# honda-z50a-regulator.net
KiCad netlist of a schematic drawn in EAGLE
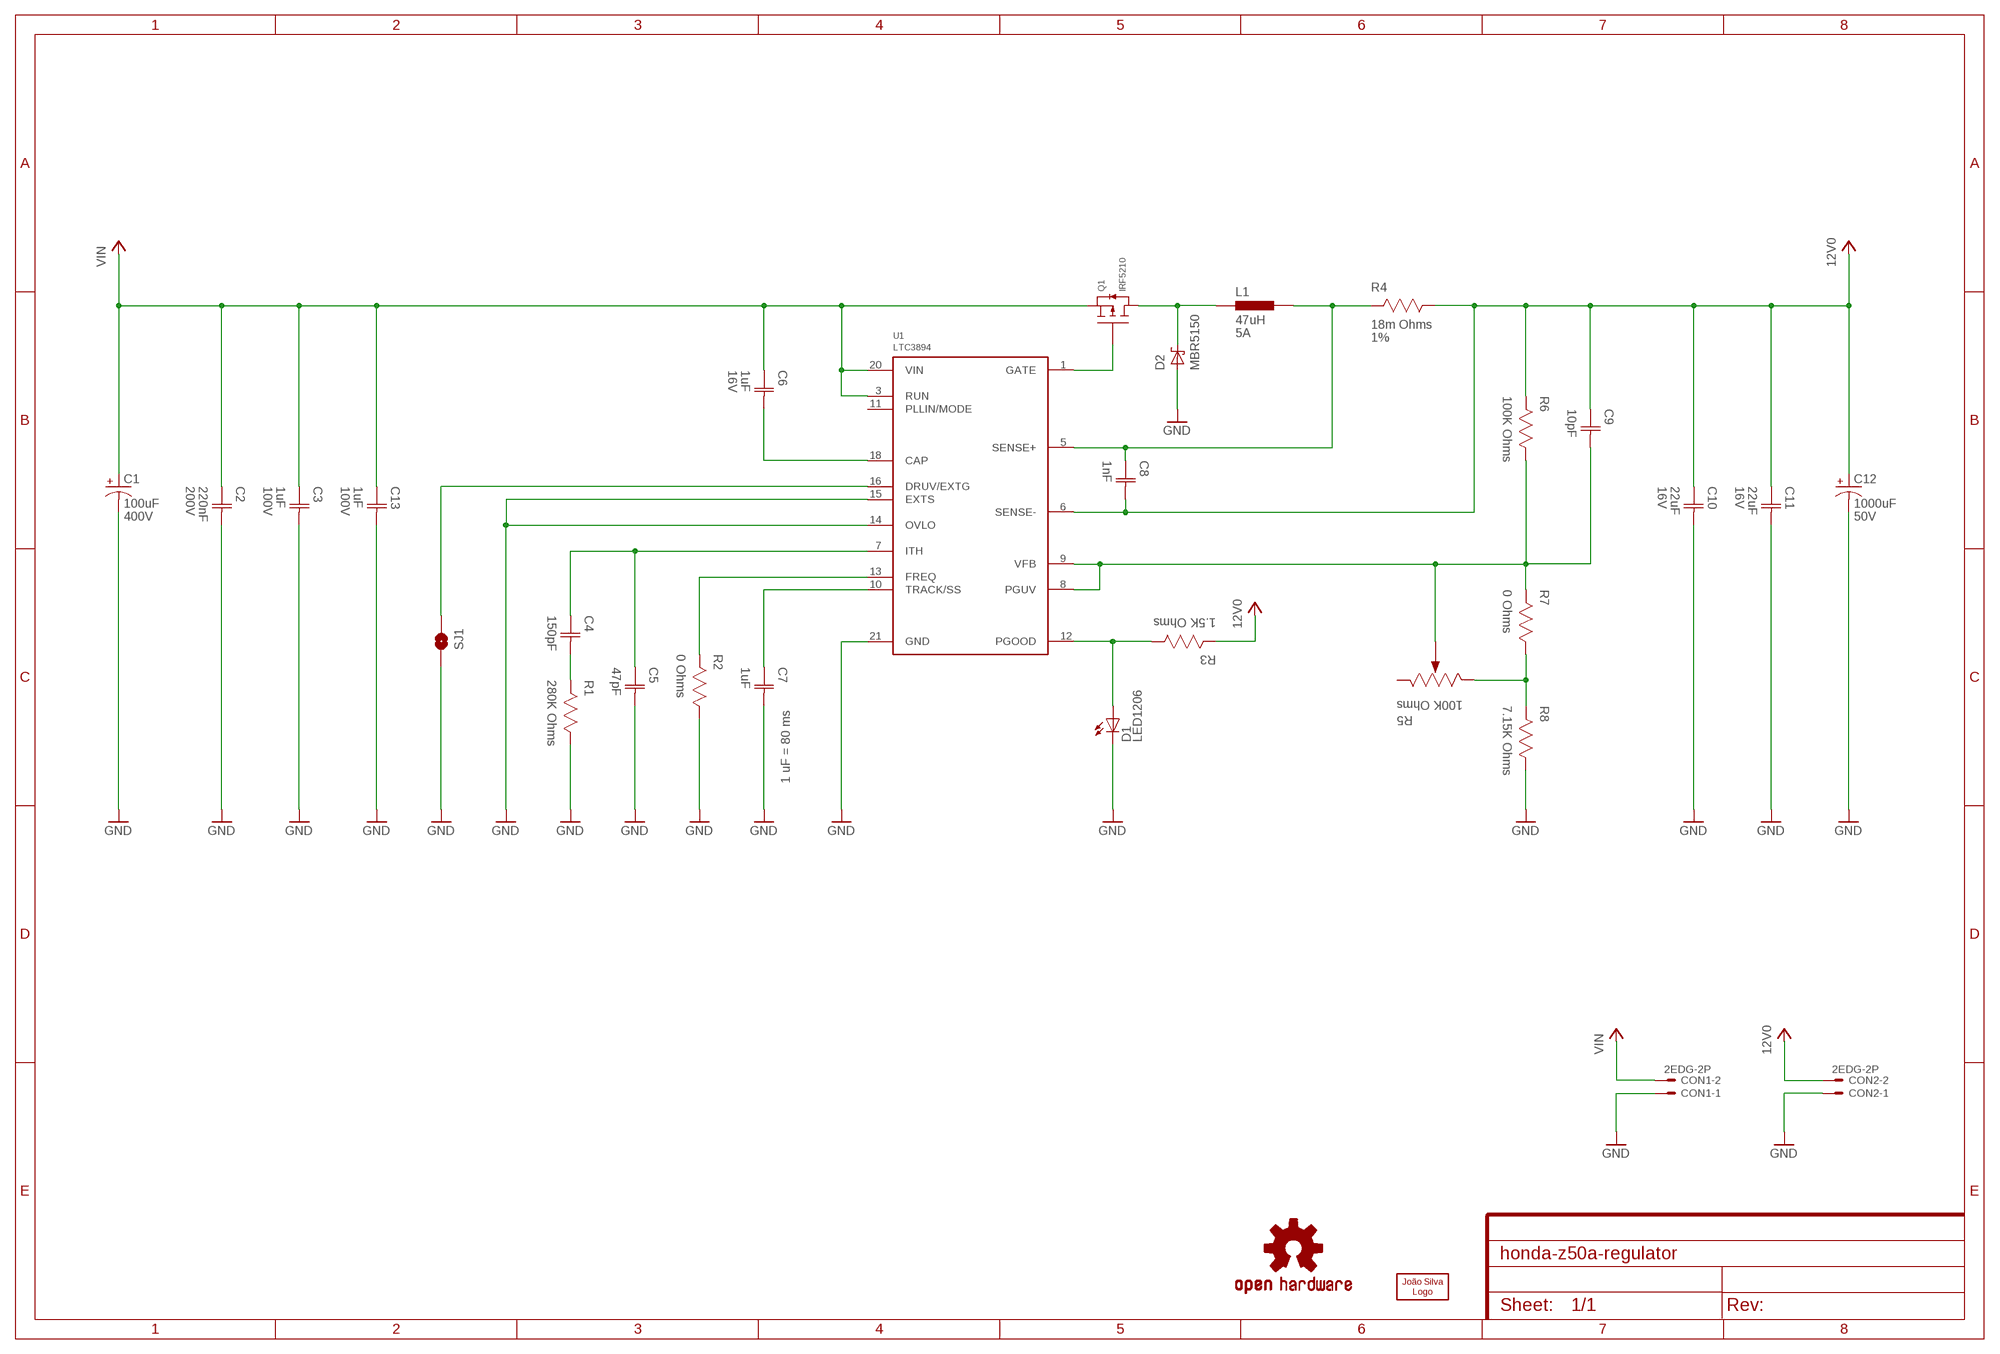
[diagram p0: schematic, sheet 1]

(export (version "E")
  (design (tool "Eeschema 10.0.6"))
  (components
    (comp (ref "C1")
      (value "100uF")
      (footprint "eagle-import:EL-CAP-18MM")
      (fields (field (name "VOLTAGE") "400V"))
      (libsource (lib "eagle-import") (part "ELETROLITIC-CAPACITOR-18MM"))
    )
    (comp (ref "C2")
      (value "220nF")
      (footprint "eagle-import:CAP1206")
      (fields (field (name "VOLTAGE") "200V"))
      (libsource (lib "eagle-import") (part "CAPACITOR-1206"))
    )
    (comp (ref "C3")
      (value "1uF")
      (footprint "eagle-import:CAP1206")
      (fields (field (name "VOLTAGE") "100V"))
      (libsource (lib "eagle-import") (part "CAPACITOR-1206"))
    )
    (comp (ref "C4")
      (value "150pF")
      (footprint "eagle-import:CAP0603")
      (libsource (lib "eagle-import") (part "CAPACITOR-0603"))
    )
    (comp (ref "C5")
      (value "47pF")
      (footprint "eagle-import:CAP0603")
      (libsource (lib "eagle-import") (part "CAPACITOR-0603"))
    )
    (comp (ref "C6")
      (value "1uF")
      (footprint "eagle-import:CAP0603")
      (fields (field (name "VOLTAGE") "16V"))
      (libsource (lib "eagle-import") (part "CAPACITOR-0603"))
    )
    (comp (ref "C7")
      (value "1uF")
      (footprint "eagle-import:CAP0603")
      (libsource (lib "eagle-import") (part "CAPACITOR-0603"))
    )
    (comp (ref "C8")
      (value "1nF")
      (footprint "eagle-import:CAP0603")
      (libsource (lib "eagle-import") (part "CAPACITOR-0603"))
    )
    (comp (ref "C9")
      (value "10pF")
      (footprint "eagle-import:CAP0603")
      (libsource (lib "eagle-import") (part "CAPACITOR-0603"))
    )
    (comp (ref "C10")
      (value "22uF")
      (footprint "eagle-import:CAP1206")
      (fields (field (name "VOLTAGE") "16V"))
      (libsource (lib "eagle-import") (part "CAPACITOR-1206"))
    )
    (comp (ref "C11")
      (value "22uF")
      (footprint "eagle-import:CAP1206")
      (fields (field (name "VOLTAGE") "16V"))
      (libsource (lib "eagle-import") (part "CAPACITOR-1206"))
    )
    (comp (ref "C12")
      (value "1000uF")
      (footprint "eagle-import:EL-CAP-13MM")
      (fields (field (name "VOLTAGE") "50V"))
      (libsource (lib "eagle-import") (part "ELETROLITIC-CAPACITOR-13MM"))
    )
    (comp (ref "C13")
      (value "1uF")
      (footprint "eagle-import:CAP1206")
      (fields (field (name "VOLTAGE") "100V"))
      (libsource (lib "eagle-import") (part "CAPACITOR-1206"))
    )
    (comp (ref "CON1")
      (value "2EDG-2P")
      (footprint "eagle-import:2EDG-2P")
      (libsource (lib "eagle-import") (part "2EDG-2P"))
    )
    (comp (ref "CON2")
      (value "2EDG-2P")
      (footprint "eagle-import:2EDG-2P")
      (libsource (lib "eagle-import") (part "2EDG-2P"))
    )
    (comp (ref "D1")
      (value "LED1206")
      (footprint "eagle-import:1206")
      (libsource (lib "eagle-import") (part "LED1206"))
    )
    (comp (ref "D2")
      (value "MBR5150")
      (footprint "eagle-import:DO201AD")
      (libsource (lib "eagle-import") (part "MBR5150"))
    )
    (comp (ref "L1")
      (value "47uH")
      (footprint "eagle-import:IND1365")
      (fields (field (name "CURRENT") "5A"))
      (libsource (lib "eagle-import") (part "INDUCTOR-13X13X6.5MM"))
    )
    (comp (ref "LOGO1")
      (value "OSHW-LOGOS")
      (footprint "eagle-import:OSHW-LOGO-S")
      (libsource (lib "eagle-import") (part "OSHW-LOGOS"))
    )
    (comp (ref "LOGO2")
      (value "JS-5MM")
      (footprint "eagle-import:JS_5MM")
      (libsource (lib "eagle-import") (part "JS-5MM"))
    )
    (comp (ref "Q1")
      (value "IRF5210")
      (footprint "eagle-import:TO262-HS")
      (libsource (lib "eagle-import") (part "IRF5210"))
    )
    (comp (ref "R1")
      (value "280K Ohms")
      (footprint "eagle-import:RES0603")
      (libsource (lib "eagle-import") (part "RESISTOR-0603"))
    )
    (comp (ref "R2")
      (value "0 Ohms")
      (footprint "eagle-import:RES0603")
      (libsource (lib "eagle-import") (part "RESISTOR-0603"))
    )
    (comp (ref "R3")
      (value "1.5K Ohms")
      (footprint "eagle-import:RES0603")
      (libsource (lib "eagle-import") (part "RESISTOR-0603"))
    )
    (comp (ref "R4")
      (value "18m Ohms")
      (footprint "eagle-import:RES2512")
      (fields (field (name "TOLERANCE") "1%"))
      (libsource (lib "eagle-import") (part "RESISTOR-2512"))
    )
    (comp (ref "R5")
      (value "100K Ohms")
      (footprint "eagle-import:TRIMMER")
      (libsource (lib "eagle-import") (part "POTENTIOMETER-TH"))
    )
    (comp (ref "R6")
      (value "100K Ohms")
      (footprint "eagle-import:RES0603")
      (libsource (lib "eagle-import") (part "RESISTOR-0603"))
    )
    (comp (ref "R7")
      (value "0 Ohms")
      (footprint "eagle-import:RES0603")
      (libsource (lib "eagle-import") (part "RESISTOR-0603"))
    )
    (comp (ref "R8")
      (value "7.15K Ohms")
      (footprint "eagle-import:RES0603")
      (libsource (lib "eagle-import") (part "RESISTOR-0603"))
    )
    (comp (ref "SJ1")
      (value "SJS")
      (footprint "eagle-import:SJ_S")
      (libsource (lib "eagle-import") (part "SJS"))
    )
    (comp (ref "U1")
      (value "LTC3894")
      (footprint "eagle-import:MSOP20_HV_EP")
      (libsource (lib "eagle-import") (part "LTC3894"))
    )
  )
  (nets
    (net (code "1") (name "12V0") (class "Default")
      (node (ref "C10") (pin "1") (pinfunction "C1_1") (pintype "passive"))
      (node (ref "C11") (pin "1") (pinfunction "C1_1") (pintype "passive"))
      (node (ref "C12") (pin "+") (pinfunction "+_+") (pintype "passive"))
      (node (ref "C8") (pin "2") (pinfunction "C2_2") (pintype "passive"))
      (node (ref "C9") (pin "1") (pinfunction "C1_1") (pintype "passive"))
      (node (ref "CON2") (pin "P$2") (pinfunction "S_P$2") (pintype "passive"))
      (node (ref "R3") (pin "2") (pinfunction "2_2") (pintype "passive"))
      (node (ref "R4") (pin "1") (pinfunction "1_1") (pintype "passive"))
      (node (ref "R6") (pin "2") (pinfunction "2_2") (pintype "passive"))
      (node (ref "U1") (pin "6") (pinfunction "SENSE-_6") (pintype "bidirectional"))
    )
    (net (code "2") (name "GND") (class "Default")
      (node (ref "C1") (pin "-") (pinfunction "-_-") (pintype "passive"))
      (node (ref "C10") (pin "2") (pinfunction "C2_2") (pintype "passive"))
      (node (ref "C11") (pin "2") (pinfunction "C2_2") (pintype "passive"))
      (node (ref "C12") (pin "-") (pinfunction "-_-") (pintype "passive"))
      (node (ref "C13") (pin "2") (pinfunction "C2_2") (pintype "passive"))
      (node (ref "C2") (pin "2") (pinfunction "C2_2") (pintype "passive"))
      (node (ref "C3") (pin "2") (pinfunction "C2_2") (pintype "passive"))
      (node (ref "C5") (pin "2") (pinfunction "C2_2") (pintype "passive"))
      (node (ref "C7") (pin "2") (pinfunction "C2_2") (pintype "passive"))
      (node (ref "CON1") (pin "P$1") (pinfunction "S_P$1") (pintype "passive"))
      (node (ref "CON2") (pin "P$1") (pinfunction "S_P$1") (pintype "passive"))
      (node (ref "D1") (pin "C") (pinfunction "C_C") (pintype "passive"))
      (node (ref "D2") (pin "A") (pinfunction "A_A") (pintype "passive"))
      (node (ref "R1") (pin "1") (pinfunction "1_1") (pintype "passive"))
      (node (ref "R2") (pin "1") (pinfunction "1_1") (pintype "passive"))
      (node (ref "R8") (pin "1") (pinfunction "1_1") (pintype "passive"))
      (node (ref "SJ1") (pin "2") (pinfunction "2_2") (pintype "passive"))
      (node (ref "U1") (pin "14") (pinfunction "OVLO_14") (pintype "bidirectional"))
      (node (ref "U1") (pin "15") (pinfunction "EXTS_15") (pintype "bidirectional"))
      (node (ref "U1") (pin "21") (pinfunction "GND_21") (pintype "bidirectional"))
    )
    (net (code "3") (name "Net-(C4-C1)") (class "Default")
      (node (ref "C4") (pin "1") (pinfunction "C1_1") (pintype "passive"))
      (node (ref "C5") (pin "1") (pinfunction "C1_1") (pintype "passive"))
      (node (ref "U1") (pin "7") (pinfunction "ITH_7") (pintype "bidirectional"))
    )
    (net (code "4") (name "Net-(C4-C2)") (class "Default")
      (node (ref "C4") (pin "2") (pinfunction "C2_2") (pintype "passive"))
      (node (ref "R1") (pin "2") (pinfunction "2_2") (pintype "passive"))
    )
    (net (code "5") (name "Net-(C6-C2)") (class "Default")
      (node (ref "C6") (pin "2") (pinfunction "C2_2") (pintype "passive"))
      (node (ref "U1") (pin "18") (pinfunction "CAP_18") (pintype "bidirectional"))
    )
    (net (code "6") (name "Net-(C7-C1)") (class "Default")
      (node (ref "C7") (pin "1") (pinfunction "C1_1") (pintype "passive"))
      (node (ref "U1") (pin "10") (pinfunction "TRACK/SS_10") (pintype "bidirectional"))
    )
    (net (code "7") (name "Net-(C8-C1)") (class "Default")
      (node (ref "C8") (pin "1") (pinfunction "C1_1") (pintype "passive"))
      (node (ref "L1") (pin "2") (pinfunction "2_2") (pintype "passive"))
      (node (ref "R4") (pin "2") (pinfunction "2_2") (pintype "passive"))
      (node (ref "U1") (pin "5") (pinfunction "SENSE+_5") (pintype "bidirectional"))
    )
    (net (code "8") (name "Net-(C9-C2)") (class "Default")
      (node (ref "C9") (pin "2") (pinfunction "C2_2") (pintype "passive"))
      (node (ref "R5") (pin "S") (pinfunction "WIPER_S") (pintype "passive"))
      (node (ref "R6") (pin "1") (pinfunction "1_1") (pintype "passive"))
      (node (ref "R7") (pin "2") (pinfunction "2_2") (pintype "passive"))
      (node (ref "U1") (pin "8") (pinfunction "PGUV_8") (pintype "bidirectional"))
      (node (ref "U1") (pin "9") (pinfunction "VFB_9") (pintype "bidirectional"))
    )
    (net (code "9") (name "Net-(D2-PadC)") (class "Default")
      (node (ref "D2") (pin "C") (pinfunction "C_C") (pintype "passive"))
      (node (ref "L1") (pin "1") (pinfunction "1_1") (pintype "passive"))
      (node (ref "Q1") (pin "D") (pinfunction "D_D") (pintype "passive"))
    )
    (net (code "10") (name "Net-(R5-CW)") (class "Default")
      (node (ref "R5") (pin "E") (pinfunction "CW_E") (pintype "passive"))
      (node (ref "R7") (pin "1") (pinfunction "1_1") (pintype "passive"))
      (node (ref "R8") (pin "2") (pinfunction "2_2") (pintype "passive"))
    )
    (net (code "11") (name "Net-(U1-DRUV{slash}EXTG)") (class "Default")
      (node (ref "SJ1") (pin "1") (pinfunction "1_1") (pintype "passive"))
      (node (ref "U1") (pin "16") (pinfunction "DRUV/EXTG_16") (pintype "bidirectional"))
    )
    (net (code "12") (name "Net-(U1-FREQ)") (class "Default")
      (node (ref "R2") (pin "2") (pinfunction "2_2") (pintype "passive"))
      (node (ref "U1") (pin "13") (pinfunction "FREQ_13") (pintype "bidirectional"))
    )
    (net (code "13") (name "Net-(U1-GATE)") (class "Default")
      (node (ref "Q1") (pin "G") (pinfunction "G_G") (pintype "passive"))
      (node (ref "U1") (pin "1") (pinfunction "GATE_1") (pintype "bidirectional"))
    )
    (net (code "14") (name "Net-(U1-PGOOD)") (class "Default")
      (node (ref "D1") (pin "A") (pinfunction "A_A") (pintype "passive"))
      (node (ref "R3") (pin "1") (pinfunction "1_1") (pintype "passive"))
      (node (ref "U1") (pin "12") (pinfunction "PGOOD_12") (pintype "bidirectional"))
    )
    (net (code "15") (name "VIN") (class "Default")
      (node (ref "C1") (pin "+") (pinfunction "+_+") (pintype "passive"))
      (node (ref "C13") (pin "1") (pinfunction "C1_1") (pintype "passive"))
      (node (ref "C2") (pin "1") (pinfunction "C1_1") (pintype "passive"))
      (node (ref "C3") (pin "1") (pinfunction "C1_1") (pintype "passive"))
      (node (ref "C6") (pin "1") (pinfunction "C1_1") (pintype "passive"))
      (node (ref "CON1") (pin "P$2") (pinfunction "S_P$2") (pintype "passive"))
      (node (ref "Q1") (pin "S") (pinfunction "S_S") (pintype "passive"))
      (node (ref "U1") (pin "20") (pinfunction "VIN_20") (pintype "bidirectional"))
      (node (ref "U1") (pin "3") (pinfunction "RUN_3") (pintype "bidirectional"))
    )
    (net (code "16") (name "unconnected-(R5-CCW-PadA)") (class "Default")
      (node (ref "R5") (pin "A") (pinfunction "CCW_A") (pintype "passive"))
    )
    (net (code "17") (name "unconnected-(U1-PLLIN{slash}MODE-Pad11)") (class "Default")
      (node (ref "U1") (pin "11") (pinfunction "PLLIN/MODE_11") (pintype "bidirectional"))
    )
  )
)
